# IO_and_Comm.net
KiCad netlist of a schematic drawn in Altium Designer
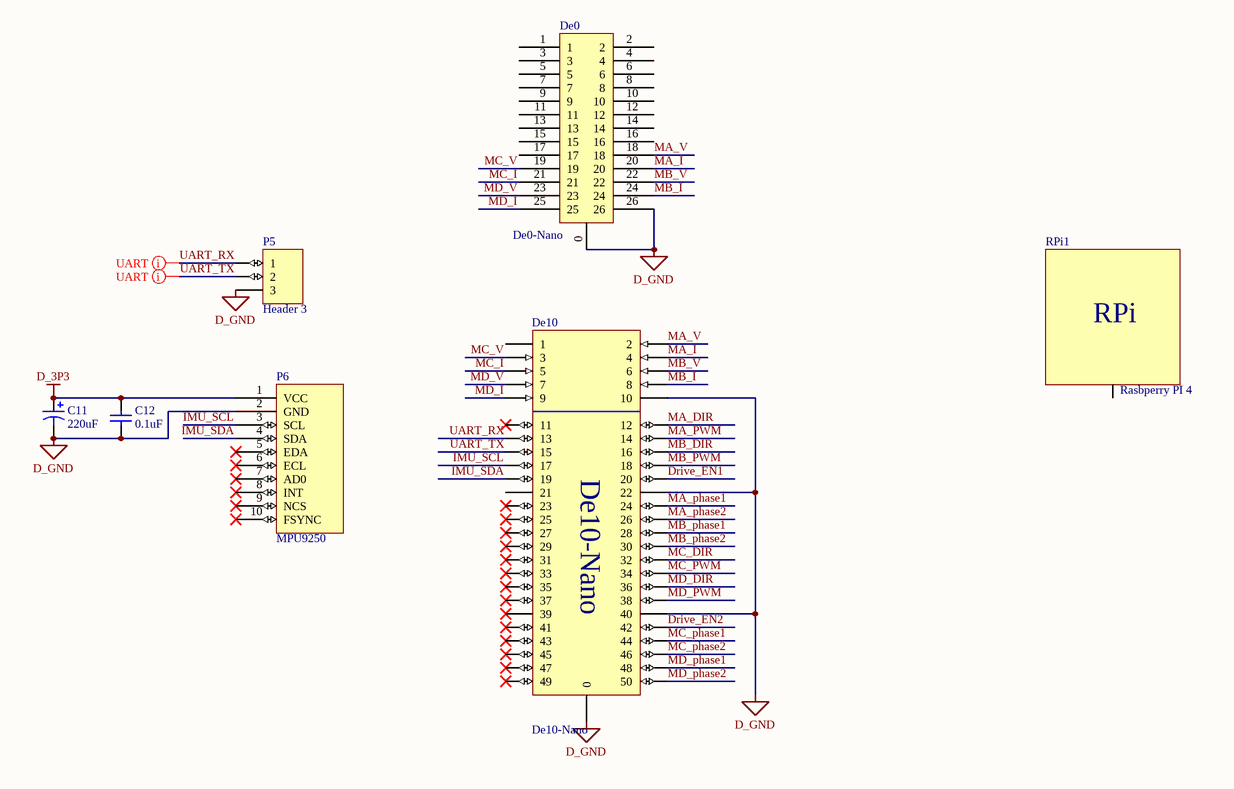
[diagram p0: IO and Comm.SchDoc]

(export (version "E")
  (design (tool "Eeschema 10.0.6"))
  (components
    (comp (ref "C11")
      (value "220uF")
      (footprint "OWMR:VZT221M1ETR-0607")
      (fields (field (name "PUBLISHER") "Altium Limited"))
      (libsource (lib "Miscellaneous Devices") (part "Cap Pol1"))
    )
    (comp (ref "C12")
      (value "0.1uF")
      (footprint "OWMR:CL10B104KA8NNNC")
      (description "25V 100nF X7R ±10% 0603  Multilayer Ceramic Capacitors MLCC - SMD/SMT ROHS")
      (fields (field (name "PUBLISHER") "Altium Limited"))
      (libsource (lib "Miscellaneous Devices") (part "Cap Semi"))
    )
    (comp (ref "De0")
      (value "De0-Nano")
      (footprint "DE0-Nano")
      (description "DE0-Nano")
      (libsource (lib "OWMR") (part "De0-Nano"))
    )
    (comp (ref "De10")
      (value "De10-Nano")
      (footprint "OWMR:De10-Nano")
      (libsource (lib "OWMR") (part "De10-Nano"))
    )
    (comp (ref "P5")
      (value "Header 3")
      (footprint "OWMR:B3B-XH-A(LF)(SN)")
      (description "1x3P XH 1 2.5mm 3 Brass Plugin,P=2.5mm  Wire To Board / Wire To Wire Connector ROHS")
      (fields (field (name "PUBLISHER") "Altium Limited"))
      (libsource (lib "Miscellaneous Connectors") (part "Header 3"))
    )
    (comp (ref "P6")
      (value "MPU9250")
      (footprint "MPU9250")
      (description "9DOF, 3 Axis Gyro, Acceleration, Magmetic")
      (libsource (lib "OWMR") (part "MPU9250"))
    )
    (comp (ref "RPi1")
      (value "Rasbperry PI 4")
      (footprint "OWMR:Raspberry Pi 4")
      (libsource (lib "OWMR") (part "Rasbperry PI 4"))
    )
  )
  (nets
    (net (code "1") (name "/Drive_EN1") (class "Default")
      (node (ref "De10") (pin "20") (pinfunction "20_20") (pintype "bidirectional"))
    )
    (net (code "2") (name "/Drive_EN2") (class "Default")
      (node (ref "De10") (pin "42") (pinfunction "42_42") (pintype "bidirectional"))
    )
    (net (code "3") (name "/IMU_SCL") (class "Default")
      (node (ref "De10") (pin "17") (pinfunction "17_17") (pintype "bidirectional"))
      (node (ref "P6") (pin "3") (pinfunction "SCL_3") (pintype "bidirectional"))
    )
    (net (code "4") (name "/IMU_SDA") (class "Default")
      (node (ref "De10") (pin "19") (pinfunction "19_19") (pintype "bidirectional"))
      (node (ref "P6") (pin "4") (pinfunction "SDA_4") (pintype "bidirectional"))
    )
    (net (code "5") (name "/MA_DIR") (class "Default")
      (node (ref "De10") (pin "12") (pinfunction "12_12") (pintype "bidirectional"))
    )
    (net (code "6") (name "/MA_I") (class "Default")
      (node (ref "De0") (pin "20") (pinfunction "20_20") (pintype "passive"))
      (node (ref "De10") (pin "4") (pinfunction "4_4") (pintype "input"))
    )
    (net (code "7") (name "/MA_PWM") (class "Default")
      (node (ref "De10") (pin "14") (pinfunction "14_14") (pintype "bidirectional"))
    )
    (net (code "8") (name "/MA_V") (class "Default")
      (node (ref "De0") (pin "18") (pinfunction "18_18") (pintype "passive"))
      (node (ref "De10") (pin "2") (pinfunction "2_2") (pintype "input"))
    )
    (net (code "9") (name "/MA_phase1") (class "Default")
      (node (ref "De10") (pin "24") (pinfunction "24_24") (pintype "bidirectional"))
    )
    (net (code "10") (name "/MA_phase2") (class "Default")
      (node (ref "De10") (pin "26") (pinfunction "26_26") (pintype "bidirectional"))
    )
    (net (code "11") (name "/MB_DIR") (class "Default")
      (node (ref "De10") (pin "16") (pinfunction "16_16") (pintype "bidirectional"))
    )
    (net (code "12") (name "/MB_I") (class "Default")
      (node (ref "De0") (pin "24") (pinfunction "24_24") (pintype "passive"))
      (node (ref "De10") (pin "8") (pinfunction "8_8") (pintype "input"))
    )
    (net (code "13") (name "/MB_PWM") (class "Default")
      (node (ref "De10") (pin "18") (pinfunction "18_18") (pintype "bidirectional"))
    )
    (net (code "14") (name "/MB_V") (class "Default")
      (node (ref "De0") (pin "22") (pinfunction "22_22") (pintype "passive"))
      (node (ref "De10") (pin "6") (pinfunction "6_6") (pintype "input"))
    )
    (net (code "15") (name "/MB_phase1") (class "Default")
      (node (ref "De10") (pin "28") (pinfunction "28_28") (pintype "bidirectional"))
    )
    (net (code "16") (name "/MB_phase2") (class "Default")
      (node (ref "De10") (pin "30") (pinfunction "30_30") (pintype "bidirectional"))
    )
    (net (code "17") (name "/MC_DIR") (class "Default")
      (node (ref "De10") (pin "32") (pinfunction "32_32") (pintype "bidirectional"))
    )
    (net (code "18") (name "/MC_I") (class "Default")
      (node (ref "De0") (pin "21") (pinfunction "21_21") (pintype "passive"))
      (node (ref "De10") (pin "5") (pinfunction "5_5") (pintype "input"))
    )
    (net (code "19") (name "/MC_PWM") (class "Default")
      (node (ref "De10") (pin "34") (pinfunction "34_34") (pintype "bidirectional"))
    )
    (net (code "20") (name "/MC_V") (class "Default")
      (node (ref "De0") (pin "19") (pinfunction "19_19") (pintype "passive"))
      (node (ref "De10") (pin "3") (pinfunction "3_3") (pintype "input"))
    )
    (net (code "21") (name "/MC_phase1") (class "Default")
      (node (ref "De10") (pin "44") (pinfunction "44_44") (pintype "bidirectional"))
    )
    (net (code "22") (name "/MC_phase2") (class "Default")
      (node (ref "De10") (pin "46") (pinfunction "46_46") (pintype "bidirectional"))
    )
    (net (code "23") (name "/MD_DIR") (class "Default")
      (node (ref "De10") (pin "36") (pinfunction "36_36") (pintype "bidirectional"))
    )
    (net (code "24") (name "/MD_I") (class "Default")
      (node (ref "De0") (pin "25") (pinfunction "25_25") (pintype "passive"))
      (node (ref "De10") (pin "9") (pinfunction "9_9") (pintype "input"))
    )
    (net (code "25") (name "/MD_PWM") (class "Default")
      (node (ref "De10") (pin "38") (pinfunction "38_38") (pintype "bidirectional"))
    )
    (net (code "26") (name "/MD_V") (class "Default")
      (node (ref "De0") (pin "23") (pinfunction "23_23") (pintype "passive"))
      (node (ref "De10") (pin "7") (pinfunction "7_7") (pintype "input"))
    )
    (net (code "27") (name "/MD_phase1") (class "Default")
      (node (ref "De10") (pin "48") (pinfunction "48_48") (pintype "bidirectional"))
    )
    (net (code "28") (name "/MD_phase2") (class "Default")
      (node (ref "De10") (pin "50") (pinfunction "50_50") (pintype "bidirectional"))
    )
    (net (code "29") (name "/UART_RX") (class "Default")
      (node (ref "De10") (pin "13") (pinfunction "13_13") (pintype "bidirectional"))
      (node (ref "P5") (pin "1") (pinfunction "1_1") (pintype "bidirectional"))
    )
    (net (code "30") (name "/UART_TX") (class "Default")
      (node (ref "De10") (pin "15") (pinfunction "15_15") (pintype "bidirectional"))
      (node (ref "P5") (pin "2") (pinfunction "2_2") (pintype "bidirectional"))
    )
    (net (code "31") (name "D_3P3") (class "Default")
      (node (ref "C11") (pin "1") (pinfunction "1_1") (pintype "passive"))
      (node (ref "C12") (pin "2") (pinfunction "2_2") (pintype "passive"))
      (node (ref "P6") (pin "1") (pinfunction "VCC_1") (pintype "power_in"))
    )
    (net (code "32") (name "D_GND") (class "Default")
      (node (ref "C11") (pin "2") (pinfunction "2_2") (pintype "passive"))
      (node (ref "C12") (pin "1") (pinfunction "1_1") (pintype "passive"))
      (node (ref "De0") (pin "0") (pinfunction "0_0") (pintype "passive"))
      (node (ref "De0") (pin "26") (pinfunction "26_26") (pintype "passive"))
      (node (ref "De10") (pin "0") (pinfunction "0_0") (pintype "power_in"))
      (node (ref "De10") (pin "10") (pinfunction "10_10") (pintype "power_in"))
      (node (ref "De10") (pin "22") (pinfunction "22_22") (pintype "power_in"))
      (node (ref "De10") (pin "40") (pinfunction "40_40") (pintype "power_in"))
      (node (ref "P5") (pin "3") (pinfunction "3_3") (pintype "power_in"))
      (node (ref "P6") (pin "2") (pinfunction "GND_2") (pintype "power_in"))
    )
    (net (code "33") (name "unconnected-(De0-Pad1)") (class "Default")
      (node (ref "De0") (pin "1") (pinfunction "1_1") (pintype "passive"))
    )
    (net (code "34") (name "unconnected-(De0-Pad2)") (class "Default")
      (node (ref "De0") (pin "2") (pinfunction "2_2") (pintype "passive"))
    )
    (net (code "35") (name "unconnected-(De0-Pad3)") (class "Default")
      (node (ref "De0") (pin "3") (pinfunction "3_3") (pintype "passive"))
    )
    (net (code "36") (name "unconnected-(De0-Pad4)") (class "Default")
      (node (ref "De0") (pin "4") (pinfunction "4_4") (pintype "passive"))
    )
    (net (code "37") (name "unconnected-(De0-Pad5)") (class "Default")
      (node (ref "De0") (pin "5") (pinfunction "5_5") (pintype "passive"))
    )
    (net (code "38") (name "unconnected-(De0-Pad6)") (class "Default")
      (node (ref "De0") (pin "6") (pinfunction "6_6") (pintype "passive"))
    )
    (net (code "39") (name "unconnected-(De0-Pad7)") (class "Default")
      (node (ref "De0") (pin "7") (pinfunction "7_7") (pintype "passive"))
    )
    (net (code "40") (name "unconnected-(De0-Pad8)") (class "Default")
      (node (ref "De0") (pin "8") (pinfunction "8_8") (pintype "passive"))
    )
    (net (code "41") (name "unconnected-(De0-Pad9)") (class "Default")
      (node (ref "De0") (pin "9") (pinfunction "9_9") (pintype "passive"))
    )
    (net (code "42") (name "unconnected-(De0-Pad10)") (class "Default")
      (node (ref "De0") (pin "10") (pinfunction "10_10") (pintype "passive"))
    )
    (net (code "43") (name "unconnected-(De0-Pad11)") (class "Default")
      (node (ref "De0") (pin "11") (pinfunction "11_11") (pintype "passive"))
    )
    (net (code "44") (name "unconnected-(De0-Pad12)") (class "Default")
      (node (ref "De0") (pin "12") (pinfunction "12_12") (pintype "passive"))
    )
    (net (code "45") (name "unconnected-(De0-Pad13)") (class "Default")
      (node (ref "De0") (pin "13") (pinfunction "13_13") (pintype "passive"))
    )
    (net (code "46") (name "unconnected-(De0-Pad14)") (class "Default")
      (node (ref "De0") (pin "14") (pinfunction "14_14") (pintype "passive"))
    )
    (net (code "47") (name "unconnected-(De0-Pad15)") (class "Default")
      (node (ref "De0") (pin "15") (pinfunction "15_15") (pintype "passive"))
    )
    (net (code "48") (name "unconnected-(De0-Pad16)") (class "Default")
      (node (ref "De0") (pin "16") (pinfunction "16_16") (pintype "passive"))
    )
    (net (code "49") (name "unconnected-(De0-Pad17)") (class "Default")
      (node (ref "De0") (pin "17") (pinfunction "17_17") (pintype "passive"))
    )
    (net (code "50") (name "unconnected-(De10-Pad1)") (class "Default")
      (node (ref "De10") (pin "1") (pinfunction "1_1") (pintype "power_in"))
    )
    (net (code "51") (name "unconnected-(De10-Pad11)") (class "Default")
      (node (ref "De10") (pin "11") (pinfunction "11_11") (pintype "bidirectional+no_connect"))
    )
    (net (code "52") (name "unconnected-(De10-Pad21)") (class "Default")
      (node (ref "De10") (pin "21") (pinfunction "21_21") (pintype "power_in"))
    )
    (net (code "53") (name "unconnected-(De10-Pad23)") (class "Default")
      (node (ref "De10") (pin "23") (pinfunction "23_23") (pintype "bidirectional+no_connect"))
    )
    (net (code "54") (name "unconnected-(De10-Pad25)") (class "Default")
      (node (ref "De10") (pin "25") (pinfunction "25_25") (pintype "bidirectional+no_connect"))
    )
    (net (code "55") (name "unconnected-(De10-Pad27)") (class "Default")
      (node (ref "De10") (pin "27") (pinfunction "27_27") (pintype "bidirectional+no_connect"))
    )
    (net (code "56") (name "unconnected-(De10-Pad29)") (class "Default")
      (node (ref "De10") (pin "29") (pinfunction "29_29") (pintype "bidirectional+no_connect"))
    )
    (net (code "57") (name "unconnected-(De10-Pad31)") (class "Default")
      (node (ref "De10") (pin "31") (pinfunction "31_31") (pintype "bidirectional+no_connect"))
    )
    (net (code "58") (name "unconnected-(De10-Pad33)") (class "Default")
      (node (ref "De10") (pin "33") (pinfunction "33_33") (pintype "bidirectional+no_connect"))
    )
    (net (code "59") (name "unconnected-(De10-Pad35)") (class "Default")
      (node (ref "De10") (pin "35") (pinfunction "35_35") (pintype "bidirectional+no_connect"))
    )
    (net (code "60") (name "unconnected-(De10-Pad37)") (class "Default")
      (node (ref "De10") (pin "37") (pinfunction "37_37") (pintype "bidirectional+no_connect"))
    )
    (net (code "61") (name "unconnected-(De10-Pad39)") (class "Default")
      (node (ref "De10") (pin "39") (pinfunction "39_39") (pintype "power_in+no_connect"))
    )
    (net (code "62") (name "unconnected-(De10-Pad41)") (class "Default")
      (node (ref "De10") (pin "41") (pinfunction "41_41") (pintype "bidirectional+no_connect"))
    )
    (net (code "63") (name "unconnected-(De10-Pad43)") (class "Default")
      (node (ref "De10") (pin "43") (pinfunction "43_43") (pintype "bidirectional+no_connect"))
    )
    (net (code "64") (name "unconnected-(De10-Pad45)") (class "Default")
      (node (ref "De10") (pin "45") (pinfunction "45_45") (pintype "bidirectional+no_connect"))
    )
    (net (code "65") (name "unconnected-(De10-Pad47)") (class "Default")
      (node (ref "De10") (pin "47") (pinfunction "47_47") (pintype "bidirectional+no_connect"))
    )
    (net (code "66") (name "unconnected-(De10-Pad49)") (class "Default")
      (node (ref "De10") (pin "49") (pinfunction "49_49") (pintype "bidirectional+no_connect"))
    )
    (net (code "67") (name "unconnected-(P6-AD0-Pad7)") (class "Default")
      (node (ref "P6") (pin "7") (pinfunction "AD0_7") (pintype "bidirectional+no_connect"))
    )
    (net (code "68") (name "unconnected-(P6-ECL-Pad6)") (class "Default")
      (node (ref "P6") (pin "6") (pinfunction "ECL_6") (pintype "bidirectional+no_connect"))
    )
    (net (code "69") (name "unconnected-(P6-EDA-Pad5)") (class "Default")
      (node (ref "P6") (pin "5") (pinfunction "EDA_5") (pintype "bidirectional+no_connect"))
    )
    (net (code "70") (name "unconnected-(P6-FSYNC-Pad10)") (class "Default")
      (node (ref "P6") (pin "10") (pinfunction "FSYNC_10") (pintype "bidirectional+no_connect"))
    )
    (net (code "71") (name "unconnected-(P6-INT-Pad8)") (class "Default")
      (node (ref "P6") (pin "8") (pinfunction "INT_8") (pintype "bidirectional+no_connect"))
    )
    (net (code "72") (name "unconnected-(P6-NCS-Pad9)") (class "Default")
      (node (ref "P6") (pin "9") (pinfunction "NCS_9") (pintype "bidirectional+no_connect"))
    )
    (net (code "73") (name "unconnected-(RPi1-Pad1)") (class "Default")
      (node (ref "RPi1") (pin "1") (pinfunction "1_1") (pintype "passive"))
    )
  )
)
